# w550io_Teensy_DMX.net
KiCad netlist of a schematic drawn in EAGLE
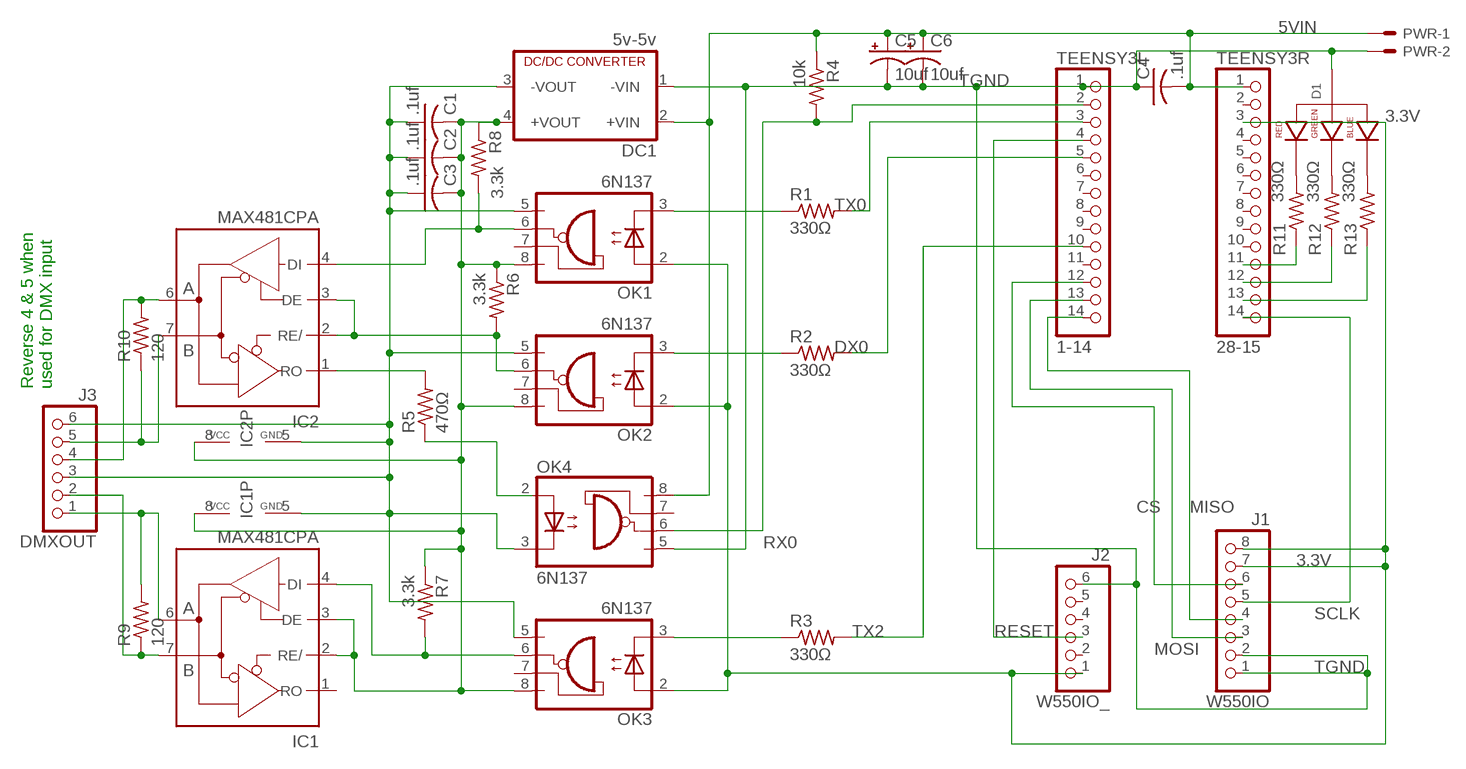
[diagram p0: schematic, sheet 1]

(export (version "E")
  (design (tool "Eeschema 10.0.6"))
  (components
    (comp (ref "C1")
      (value ".1uf")
      (footprint "eagle-import:C050-024X044")
      (libsource (lib "eagle-import") (part "C-US050-024X044"))
    )
    (comp (ref "C2")
      (value ".1uf")
      (footprint "eagle-import:C050-024X044")
      (libsource (lib "eagle-import") (part "C-US050-024X044"))
    )
    (comp (ref "C3")
      (value ".1uf")
      (footprint "eagle-import:C050-024X044")
      (libsource (lib "eagle-import") (part "C-US050-024X044"))
    )
    (comp (ref "C4")
      (value ".1uf")
      (footprint "eagle-import:C050-024X044")
      (libsource (lib "eagle-import") (part "C-US050-024X044"))
    )
    (comp (ref "C5")
      (value "10uf")
      (footprint "eagle-import:B45181B")
      (libsource (lib "eagle-import") (part "CPOL-USB45181B"))
    )
    (comp (ref "C6")
      (value "10uf")
      (footprint "eagle-import:B45181B")
      (libsource (lib "eagle-import") (part "CPOL-USB45181B"))
    )
    (comp (ref "D1")
      (value "LED-RGB-CA-THRUCLEAR")
      (footprint "eagle-import:LED-RGB-THRU")
      (libsource (lib "eagle-import") (part "LED-RGB-CA-THRUCLEAR"))
    )
    (comp (ref "DC1")
      (value "5v-5v")
      (footprint "eagle-import:NME")
      (fields (field (name "MF") "C & D TECHNOLOGIES, INC") (field (name "MPN") "NME1205D"))
      (libsource (lib "eagle-import") (part "NME"))
    )
    (comp (ref "DMXOUT")
      (value "J3")
      (footprint "eagle-import:1X06-BIG")
      (libsource (lib "eagle-import") (part "PINHD-1X6B"))
    )
    (comp (ref "IC1")
      (value "MAX481CPA")
      (footprint "eagle-import:DIL08")
      (fields (field (name "MPN") "MAX481CPA+"))
      (libsource (lib "eagle-import") (part "MAX481CPA"))
    )
    (comp (ref "IC2")
      (value "MAX481CPA")
      (footprint "eagle-import:DIL08")
      (fields (field (name "MPN") "MAX481CPA+"))
      (libsource (lib "eagle-import") (part "MAX481CPA"))
    )
    (comp (ref "OK1")
      (value "6N137")
      (footprint "eagle-import:DIL08")
      (libsource (lib "eagle-import") (part "6N137"))
    )
    (comp (ref "OK2")
      (value "6N137")
      (footprint "eagle-import:DIL08")
      (libsource (lib "eagle-import") (part "6N137"))
    )
    (comp (ref "OK3")
      (value "6N137")
      (footprint "eagle-import:DIL08")
      (libsource (lib "eagle-import") (part "6N137"))
    )
    (comp (ref "OK4")
      (value "6N137")
      (footprint "eagle-import:DIL08")
      (libsource (lib "eagle-import") (part "6N137"))
    )
    (comp (ref "PWR")
      (value "22-23-2021")
      (footprint "eagle-import:22-23-2021")
      (fields (field (name "MF") "MOLEX"))
      (libsource (lib "eagle-import") (part "22-23-2021"))
    )
    (comp (ref "R1")
      (value "330Ω")
      (footprint "eagle-import:0204_5")
      (libsource (lib "eagle-import") (part "R-US_0204/5"))
    )
    (comp (ref "R2")
      (value "330Ω")
      (footprint "eagle-import:0204_5")
      (libsource (lib "eagle-import") (part "R-US_0204/5"))
    )
    (comp (ref "R3")
      (value "330Ω")
      (footprint "eagle-import:0204_5")
      (libsource (lib "eagle-import") (part "R-US_0204/5"))
    )
    (comp (ref "R4")
      (value "10k")
      (footprint "eagle-import:0204_5")
      (libsource (lib "eagle-import") (part "R-US_0204/5"))
    )
    (comp (ref "R5")
      (value "470Ω")
      (footprint "eagle-import:0204_5")
      (libsource (lib "eagle-import") (part "R-US_0204/5"))
    )
    (comp (ref "R6")
      (value "3.3k")
      (footprint "eagle-import:0204_5")
      (libsource (lib "eagle-import") (part "R-US_0204/5"))
    )
    (comp (ref "R7")
      (value "3.3k")
      (footprint "eagle-import:0204_5")
      (libsource (lib "eagle-import") (part "R-US_0204/5"))
    )
    (comp (ref "R8")
      (value "3.3k")
      (footprint "eagle-import:0204_5")
      (libsource (lib "eagle-import") (part "R-US_0204/5"))
    )
    (comp (ref "R9")
      (value "120")
      (footprint "eagle-import:0204_5")
      (libsource (lib "eagle-import") (part "R-US_0204/5"))
    )
    (comp (ref "R10")
      (value "120")
      (footprint "eagle-import:0204_5")
      (libsource (lib "eagle-import") (part "R-US_0204/5"))
    )
    (comp (ref "R11")
      (value "330Ω")
      (footprint "eagle-import:0204_5")
      (libsource (lib "eagle-import") (part "R-US_0204/5"))
    )
    (comp (ref "R12")
      (value "330Ω")
      (footprint "eagle-import:0204_5")
      (libsource (lib "eagle-import") (part "R-US_0204/5"))
    )
    (comp (ref "R13")
      (value "330Ω")
      (footprint "eagle-import:0204_5")
      (libsource (lib "eagle-import") (part "R-US_0204/5"))
    )
    (comp (ref "TEENSY3L")
      (value "1-14")
      (footprint "eagle-import:1X14")
      (libsource (lib "eagle-import") (part "PINHD-1X14"))
    )
    (comp (ref "TEENSY3R")
      (value "28-15")
      (footprint "eagle-import:1X14")
      (libsource (lib "eagle-import") (part "PINHD-1X14"))
    )
    (comp (ref "W550IO")
      (value "J1")
      (footprint "eagle-import:1X08-BIG")
      (libsource (lib "eagle-import") (part "PINHD-1X8BIG"))
    )
    (comp (ref "W550IO_")
      (value "J2")
      (footprint "eagle-import:1X06-BIG")
      (libsource (lib "eagle-import") (part "PINHD-1X6B"))
    )
  )
  (nets
    (net (code "1") (name "/3.3V") (class "Default")
      (node (ref "OK1") (pin "2") (pinfunction "A_2") (pintype "passive"))
      (node (ref "OK2") (pin "2") (pinfunction "A_2") (pintype "passive"))
      (node (ref "OK3") (pin "2") (pinfunction "A_2") (pintype "passive"))
      (node (ref "TEENSY3R") (pin "3") (pinfunction "3_3") (pintype "passive"))
      (node (ref "W550IO") (pin "7") (pinfunction "7_7") (pintype "passive"))
      (node (ref "W550IO") (pin "8") (pinfunction "8_8") (pintype "passive"))
      (node (ref "W550IO_") (pin "1") (pinfunction "1_1") (pintype "passive"))
    )
    (net (code "2") (name "/5VIN") (class "Default")
      (node (ref "C4") (pin "2") (pinfunction "2_2") (pintype "passive"))
      (node (ref "C5") (pin "+") (pinfunction "+_+") (pintype "passive"))
      (node (ref "C6") (pin "+") (pinfunction "+_+") (pintype "passive"))
      (node (ref "DC1") (pin "2") (pinfunction "+VIN_2") (pintype "passive"))
      (node (ref "OK4") (pin "8") (pinfunction "VCC_8") (pintype "passive"))
      (node (ref "PWR") (pin "1") (pinfunction "S_1") (pintype "passive"))
      (node (ref "R4") (pin "1") (pinfunction "1_1") (pintype "passive"))
      (node (ref "TEENSY3R") (pin "1") (pinfunction "1_1") (pintype "passive"))
    )
    (net (code "3") (name "/CS") (class "Default")
      (node (ref "TEENSY3L") (pin "12") (pinfunction "12_12") (pintype "passive"))
      (node (ref "W550IO") (pin "6") (pinfunction "6_6") (pintype "passive"))
    )
    (net (code "4") (name "/DX0") (class "Default")
      (node (ref "R2") (pin "2") (pinfunction "2_2") (pintype "passive"))
      (node (ref "TEENSY3L") (pin "5") (pinfunction "5_5") (pintype "passive"))
    )
    (net (code "5") (name "/MISO") (class "Default")
      (node (ref "TEENSY3L") (pin "14") (pinfunction "14_14") (pintype "passive"))
      (node (ref "W550IO") (pin "4") (pinfunction "4_4") (pintype "passive"))
    )
    (net (code "6") (name "/MOSI") (class "Default")
      (node (ref "TEENSY3L") (pin "13") (pinfunction "13_13") (pintype "passive"))
      (node (ref "W550IO") (pin "3") (pinfunction "3_3") (pintype "passive"))
    )
    (net (code "7") (name "/RESET") (class "Default")
      (node (ref "TEENSY3L") (pin "4") (pinfunction "4_4") (pintype "passive"))
      (node (ref "W550IO_") (pin "3") (pinfunction "3_3") (pintype "passive"))
    )
    (net (code "8") (name "/RX0") (class "Default")
      (node (ref "OK4") (pin "6") (pinfunction "VO_6") (pintype "passive"))
      (node (ref "R4") (pin "2") (pinfunction "2_2") (pintype "passive"))
      (node (ref "TEENSY3L") (pin "2") (pinfunction "2_2") (pintype "passive"))
    )
    (net (code "9") (name "/SCLK") (class "Default")
      (node (ref "TEENSY3R") (pin "14") (pinfunction "14_14") (pintype "passive"))
      (node (ref "W550IO") (pin "5") (pinfunction "5_5") (pintype "passive"))
    )
    (net (code "10") (name "/TGND") (class "Default")
      (node (ref "C4") (pin "1") (pinfunction "1_1") (pintype "passive"))
      (node (ref "C5") (pin "-") (pinfunction "-_-") (pintype "passive"))
      (node (ref "C6") (pin "-") (pinfunction "-_-") (pintype "passive"))
      (node (ref "D1") (pin "2") (pinfunction "ANODE_2") (pintype "bidirectional"))
      (node (ref "DC1") (pin "1") (pinfunction "-VIN_1") (pintype "passive"))
      (node (ref "OK4") (pin "5") (pinfunction "GND_5") (pintype "passive"))
      (node (ref "PWR") (pin "2") (pinfunction "S_2") (pintype "passive"))
      (node (ref "TEENSY3L") (pin "1") (pinfunction "1_1") (pintype "passive"))
      (node (ref "W550IO") (pin "1") (pinfunction "1_1") (pintype "passive"))
      (node (ref "W550IO") (pin "2") (pinfunction "2_2") (pintype "passive"))
      (node (ref "W550IO_") (pin "6") (pinfunction "6_6") (pintype "passive"))
    )
    (net (code "11") (name "/TX0") (class "Default")
      (node (ref "R1") (pin "2") (pinfunction "2_2") (pintype "passive"))
      (node (ref "TEENSY3L") (pin "3") (pinfunction "3_3") (pintype "passive"))
    )
    (net (code "12") (name "/TX2") (class "Default")
      (node (ref "R3") (pin "2") (pinfunction "2_2") (pintype "passive"))
      (node (ref "TEENSY3L") (pin "10") (pinfunction "10_10") (pintype "passive"))
    )
    (net (code "13") (name "Net-(D1-BLUE_CATHODE)") (class "Default")
      (node (ref "D1") (pin "4") (pinfunction "BLUE_CATHODE_4") (pintype "bidirectional"))
      (node (ref "R13") (pin "2") (pinfunction "2_2") (pintype "passive"))
    )
    (net (code "14") (name "Net-(D1-GREEN_CATHODE)") (class "Default")
      (node (ref "D1") (pin "3") (pinfunction "GREEN_CATHODE_3") (pintype "bidirectional"))
      (node (ref "R12") (pin "2") (pinfunction "2_2") (pintype "passive"))
    )
    (net (code "15") (name "Net-(D1-RED_CATHODE)") (class "Default")
      (node (ref "D1") (pin "1") (pinfunction "RED_CATHODE_1") (pintype "bidirectional"))
      (node (ref "R11") (pin "2") (pinfunction "2_2") (pintype "passive"))
    )
    (net (code "16") (name "Net-(DC1-+VOUT)") (class "Default")
      (node (ref "C1") (pin "2") (pinfunction "2_2") (pintype "passive"))
      (node (ref "C2") (pin "2") (pinfunction "2_2") (pintype "passive"))
      (node (ref "C3") (pin "2") (pinfunction "2_2") (pintype "passive"))
      (node (ref "DC1") (pin "4") (pinfunction "+VOUT_4") (pintype "passive"))
      (node (ref "IC1") (pin "2") (pinfunction "RE/_2") (pintype "input"))
      (node (ref "IC1") (pin "3") (pinfunction "DE_3") (pintype "input"))
      (node (ref "IC1") (pin "8") (pinfunction "VCC_8") (pintype "power_in"))
      (node (ref "IC2") (pin "8") (pinfunction "VCC_8") (pintype "power_in"))
      (node (ref "OK1") (pin "8") (pinfunction "VCC_8") (pintype "passive"))
      (node (ref "OK2") (pin "8") (pinfunction "VCC_8") (pintype "passive"))
      (node (ref "OK3") (pin "8") (pinfunction "VCC_8") (pintype "passive"))
      (node (ref "R6") (pin "1") (pinfunction "1_1") (pintype "passive"))
      (node (ref "R7") (pin "1") (pinfunction "1_1") (pintype "passive"))
      (node (ref "R8") (pin "1") (pinfunction "1_1") (pintype "passive"))
    )
    (net (code "17") (name "Net-(DC1--VOUT)") (class "Default")
      (node (ref "C1") (pin "1") (pinfunction "1_1") (pintype "passive"))
      (node (ref "C2") (pin "1") (pinfunction "1_1") (pintype "passive"))
      (node (ref "C3") (pin "1") (pinfunction "1_1") (pintype "passive"))
      (node (ref "DC1") (pin "3") (pinfunction "-VOUT_3") (pintype "passive"))
      (node (ref "DMXOUT") (pin "3") (pinfunction "3_3") (pintype "passive"))
      (node (ref "DMXOUT") (pin "6") (pinfunction "6_6") (pintype "passive"))
      (node (ref "IC1") (pin "5") (pinfunction "GND_5") (pintype "power_in"))
      (node (ref "IC2") (pin "5") (pinfunction "GND_5") (pintype "power_in"))
      (node (ref "OK1") (pin "5") (pinfunction "GND_5") (pintype "passive"))
      (node (ref "OK2") (pin "5") (pinfunction "GND_5") (pintype "passive"))
      (node (ref "OK3") (pin "5") (pinfunction "GND_5") (pintype "passive"))
      (node (ref "OK4") (pin "3") (pinfunction "C_3") (pintype "passive"))
    )
    (net (code "18") (name "Net-(IC1A-A)") (class "Default")
      (node (ref "DMXOUT") (pin "1") (pinfunction "1_1") (pintype "passive"))
      (node (ref "IC1") (pin "6") (pinfunction "A_6") (pintype "passive"))
      (node (ref "R9") (pin "2") (pinfunction "2_2") (pintype "passive"))
    )
    (net (code "19") (name "Net-(IC1A-B)") (class "Default")
      (node (ref "DMXOUT") (pin "2") (pinfunction "2_2") (pintype "passive"))
      (node (ref "IC1") (pin "7") (pinfunction "B_7") (pintype "passive"))
      (node (ref "R9") (pin "1") (pinfunction "1_1") (pintype "passive"))
    )
    (net (code "20") (name "Net-(IC1A-DI)") (class "Default")
      (node (ref "IC1") (pin "4") (pinfunction "DI_4") (pintype "input"))
      (node (ref "OK3") (pin "6") (pinfunction "VO_6") (pintype "passive"))
      (node (ref "R7") (pin "2") (pinfunction "2_2") (pintype "passive"))
    )
    (net (code "21") (name "Net-(IC2A-A)") (class "Default")
      (node (ref "DMXOUT") (pin "4") (pinfunction "4_4") (pintype "passive"))
      (node (ref "IC2") (pin "6") (pinfunction "A_6") (pintype "passive"))
      (node (ref "R10") (pin "2") (pinfunction "2_2") (pintype "passive"))
    )
    (net (code "22") (name "Net-(IC2A-B)") (class "Default")
      (node (ref "DMXOUT") (pin "5") (pinfunction "5_5") (pintype "passive"))
      (node (ref "IC2") (pin "7") (pinfunction "B_7") (pintype "passive"))
      (node (ref "R10") (pin "1") (pinfunction "1_1") (pintype "passive"))
    )
    (net (code "23") (name "Net-(IC2A-DE)") (class "Default")
      (node (ref "IC2") (pin "2") (pinfunction "RE/_2") (pintype "input"))
      (node (ref "IC2") (pin "3") (pinfunction "DE_3") (pintype "input"))
      (node (ref "OK2") (pin "6") (pinfunction "VO_6") (pintype "passive"))
      (node (ref "R6") (pin "2") (pinfunction "2_2") (pintype "passive"))
    )
    (net (code "24") (name "Net-(IC2A-DI)") (class "Default")
      (node (ref "IC2") (pin "4") (pinfunction "DI_4") (pintype "input"))
      (node (ref "OK1") (pin "6") (pinfunction "VO_6") (pintype "passive"))
      (node (ref "R8") (pin "2") (pinfunction "2_2") (pintype "passive"))
    )
    (net (code "25") (name "Net-(IC2A-RO)") (class "Default")
      (node (ref "IC2") (pin "1") (pinfunction "RO_1") (pintype "output"))
      (node (ref "R5") (pin "2") (pinfunction "2_2") (pintype "passive"))
    )
    (net (code "26") (name "Net-(OK1-C)") (class "Default")
      (node (ref "OK1") (pin "3") (pinfunction "C_3") (pintype "passive"))
      (node (ref "R1") (pin "1") (pinfunction "1_1") (pintype "passive"))
    )
    (net (code "27") (name "Net-(OK2-C)") (class "Default")
      (node (ref "OK2") (pin "3") (pinfunction "C_3") (pintype "passive"))
      (node (ref "R2") (pin "1") (pinfunction "1_1") (pintype "passive"))
    )
    (net (code "28") (name "Net-(OK3-C)") (class "Default")
      (node (ref "OK3") (pin "3") (pinfunction "C_3") (pintype "passive"))
      (node (ref "R3") (pin "1") (pinfunction "1_1") (pintype "passive"))
    )
    (net (code "29") (name "Net-(OK4-A)") (class "Default")
      (node (ref "OK4") (pin "2") (pinfunction "A_2") (pintype "passive"))
      (node (ref "R5") (pin "1") (pinfunction "1_1") (pintype "passive"))
    )
    (net (code "30") (name "Net-(R11-Pad1)") (class "Default")
      (node (ref "R11") (pin "1") (pinfunction "1_1") (pintype "passive"))
      (node (ref "TEENSY3R") (pin "11") (pinfunction "11_11") (pintype "passive"))
    )
    (net (code "31") (name "Net-(R12-Pad1)") (class "Default")
      (node (ref "R12") (pin "1") (pinfunction "1_1") (pintype "passive"))
      (node (ref "TEENSY3R") (pin "12") (pinfunction "12_12") (pintype "passive"))
    )
    (net (code "32") (name "Net-(R13-Pad1)") (class "Default")
      (node (ref "R13") (pin "1") (pinfunction "1_1") (pintype "passive"))
      (node (ref "TEENSY3R") (pin "13") (pinfunction "13_13") (pintype "passive"))
    )
    (net (code "33") (name "unconnected-(IC1A-RO-Pad1)") (class "Default")
      (node (ref "IC1") (pin "1") (pinfunction "RO_1") (pintype "output"))
    )
    (net (code "34") (name "unconnected-(OK1-VE-Pad7)") (class "Default")
      (node (ref "OK1") (pin "7") (pinfunction "VE_7") (pintype "passive"))
    )
    (net (code "35") (name "unconnected-(OK2-VE-Pad7)") (class "Default")
      (node (ref "OK2") (pin "7") (pinfunction "VE_7") (pintype "passive"))
    )
    (net (code "36") (name "unconnected-(OK3-VE-Pad7)") (class "Default")
      (node (ref "OK3") (pin "7") (pinfunction "VE_7") (pintype "passive"))
    )
    (net (code "37") (name "unconnected-(OK4-VE-Pad7)") (class "Default")
      (node (ref "OK4") (pin "7") (pinfunction "VE_7") (pintype "passive"))
    )
    (net (code "38") (name "unconnected-(TEENSY3L-Pad6)") (class "Default")
      (node (ref "TEENSY3L") (pin "6") (pinfunction "6_6") (pintype "passive"))
    )
    (net (code "39") (name "unconnected-(TEENSY3L-Pad7)") (class "Default")
      (node (ref "TEENSY3L") (pin "7") (pinfunction "7_7") (pintype "passive"))
    )
    (net (code "40") (name "unconnected-(TEENSY3L-Pad8)") (class "Default")
      (node (ref "TEENSY3L") (pin "8") (pinfunction "8_8") (pintype "passive"))
    )
    (net (code "41") (name "unconnected-(TEENSY3L-Pad9)") (class "Default")
      (node (ref "TEENSY3L") (pin "9") (pinfunction "9_9") (pintype "passive"))
    )
    (net (code "42") (name "unconnected-(TEENSY3L-Pad11)") (class "Default")
      (node (ref "TEENSY3L") (pin "11") (pinfunction "11_11") (pintype "passive"))
    )
    (net (code "43") (name "unconnected-(TEENSY3R-Pad2)") (class "Default")
      (node (ref "TEENSY3R") (pin "2") (pinfunction "2_2") (pintype "passive"))
    )
    (net (code "44") (name "unconnected-(TEENSY3R-Pad4)") (class "Default")
      (node (ref "TEENSY3R") (pin "4") (pinfunction "4_4") (pintype "passive"))
    )
    (net (code "45") (name "unconnected-(TEENSY3R-Pad5)") (class "Default")
      (node (ref "TEENSY3R") (pin "5") (pinfunction "5_5") (pintype "passive"))
    )
    (net (code "46") (name "unconnected-(TEENSY3R-Pad6)") (class "Default")
      (node (ref "TEENSY3R") (pin "6") (pinfunction "6_6") (pintype "passive"))
    )
    (net (code "47") (name "unconnected-(TEENSY3R-Pad7)") (class "Default")
      (node (ref "TEENSY3R") (pin "7") (pinfunction "7_7") (pintype "passive"))
    )
    (net (code "48") (name "unconnected-(TEENSY3R-Pad8)") (class "Default")
      (node (ref "TEENSY3R") (pin "8") (pinfunction "8_8") (pintype "passive"))
    )
    (net (code "49") (name "unconnected-(TEENSY3R-Pad9)") (class "Default")
      (node (ref "TEENSY3R") (pin "9") (pinfunction "9_9") (pintype "passive"))
    )
    (net (code "50") (name "unconnected-(TEENSY3R-Pad10)") (class "Default")
      (node (ref "TEENSY3R") (pin "10") (pinfunction "10_10") (pintype "passive"))
    )
    (net (code "51") (name "unconnected-(W550IO_-Pad2)") (class "Default")
      (node (ref "W550IO_") (pin "2") (pinfunction "2_2") (pintype "passive"))
    )
    (net (code "52") (name "unconnected-(W550IO_-Pad4)") (class "Default")
      (node (ref "W550IO_") (pin "4") (pinfunction "4_4") (pintype "passive"))
    )
    (net (code "53") (name "unconnected-(W550IO_-Pad5)") (class "Default")
      (node (ref "W550IO_") (pin "5") (pinfunction "5_5") (pintype "passive"))
    )
  )
)
